# voc_sensor.net
KiCad netlist of a schematic drawn in EAGLE
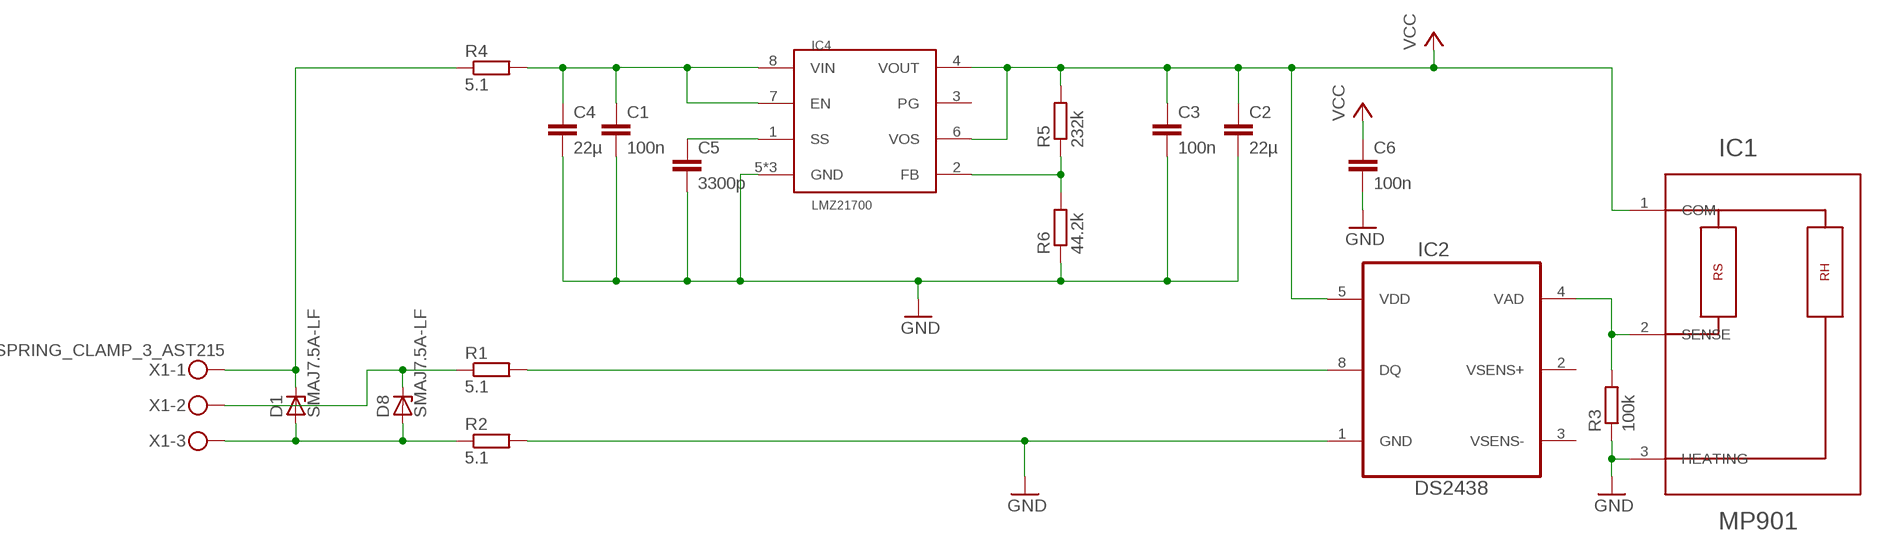
[diagram p0: schematic, sheet 1]

(export (version "E")
  (design (tool "Eeschema 10.0.6"))
  (components
    (comp (ref "C1")
      (value "100n")
      (footprint "eagle-import:C0402")
      (libsource (lib "eagle-import") (part "C-EUC0402"))
    )
    (comp (ref "C2")
      (value "22µ")
      (footprint "eagle-import:C0805K")
      (libsource (lib "eagle-import") (part "C-EUC0805K"))
    )
    (comp (ref "C3")
      (value "100n")
      (footprint "eagle-import:C0402")
      (libsource (lib "eagle-import") (part "C-EUC0402"))
    )
    (comp (ref "C4")
      (value "22µ")
      (footprint "eagle-import:C0805K")
      (libsource (lib "eagle-import") (part "C-EUC0805K"))
    )
    (comp (ref "C5")
      (value "3300p")
      (footprint "eagle-import:C0402")
      (libsource (lib "eagle-import") (part "C-EUC0402"))
    )
    (comp (ref "C6")
      (value "100n")
      (footprint "eagle-import:C0402")
      (libsource (lib "eagle-import") (part "C-EUC0402"))
    )
    (comp (ref "D1")
      (value "SMAJ7.5A-LF")
      (footprint "eagle-import:DO214AC")
      (libsource (lib "eagle-import") (part "ZENER"))
    )
    (comp (ref "D8")
      (value "SMAJ7.5A-LF")
      (footprint "eagle-import:DO214AC")
      (libsource (lib "eagle-import") (part "ZENER"))
    )
    (comp (ref "IC1")
      (value "MP901")
      (footprint "eagle-import:MP901")
      (libsource (lib "eagle-import") (part "MP901"))
    )
    (comp (ref "IC2")
      (value "DS2438")
      (footprint "eagle-import:SO-08")
      (libsource (lib "eagle-import") (part "DS2438"))
    )
    (comp (ref "IC4")
      (value "LMZ21700")
      (footprint "eagle-import:LMZ21700")
      (libsource (lib "eagle-import") (part "LMZ21700"))
    )
    (comp (ref "R1")
      (value "5.1")
      (footprint "eagle-import:R0402")
      (libsource (lib "eagle-import") (part "R-EU_R0402"))
    )
    (comp (ref "R2")
      (value "5.1")
      (footprint "eagle-import:R0402")
      (libsource (lib "eagle-import") (part "R-EU_R0402"))
    )
    (comp (ref "R3")
      (value "100k")
      (footprint "eagle-import:R0402")
      (libsource (lib "eagle-import") (part "R-EU_R0402"))
    )
    (comp (ref "R4")
      (value "5.1")
      (footprint "eagle-import:R0402")
      (libsource (lib "eagle-import") (part "R-EU_R0402"))
    )
    (comp (ref "R5")
      (value "232k")
      (footprint "eagle-import:R0402")
      (libsource (lib "eagle-import") (part "R-EU_R0402"))
    )
    (comp (ref "R6")
      (value "44.2k")
      (footprint "eagle-import:R0402")
      (libsource (lib "eagle-import") (part "R-EU_R0402"))
    )
    (comp (ref "X1")
      (value "SPRING_CLAMP_3_AST215")
      (footprint "eagle-import:AST215_3")
      (libsource (lib "eagle-import") (part "SPRING_CLAMP_3_AST215"))
    )
  )
  (nets
    (net (code "1") (name "GND") (class "Default")
      (node (ref "C1") (pin "2") (pinfunction "2_2") (pintype "passive"))
      (node (ref "C2") (pin "2") (pinfunction "2_2") (pintype "passive"))
      (node (ref "C3") (pin "2") (pinfunction "2_2") (pintype "passive"))
      (node (ref "C4") (pin "2") (pinfunction "2_2") (pintype "passive"))
      (node (ref "C5") (pin "2") (pinfunction "2_2") (pintype "passive"))
      (node (ref "C6") (pin "2") (pinfunction "2_2") (pintype "passive"))
      (node (ref "IC1") (pin "3") (pinfunction "HEATING_3") (pintype "bidirectional"))
      (node (ref "IC2") (pin "1") (pinfunction "GND_1") (pintype "passive"))
      (node (ref "IC4") (pin "5") (pinfunction "GND_5") (pintype "bidirectional"))
      (node (ref "IC4") (pin "TPAD@1") (pinfunction "GND_TPAD@1") (pintype "bidirectional"))
      (node (ref "IC4") (pin "TPAD@2") (pinfunction "GND_TPAD@2") (pintype "bidirectional"))
      (node (ref "R2") (pin "2") (pinfunction "2_2") (pintype "passive"))
      (node (ref "R3") (pin "1") (pinfunction "1_1") (pintype "passive"))
      (node (ref "R6") (pin "1") (pinfunction "1_1") (pintype "passive"))
    )
    (net (code "2") (name "Net-(D1-PadA)") (class "Default")
      (node (ref "D1") (pin "A") (pinfunction "A_A") (pintype "passive"))
      (node (ref "D8") (pin "A") (pinfunction "A_A") (pintype "passive"))
      (node (ref "R2") (pin "1") (pinfunction "1_1") (pintype "passive"))
      (node (ref "X1") (pin "3A") (pinfunction "KL_3A") (pintype "passive"))
      (node (ref "X1") (pin "3B") (pinfunction "KL_3B") (pintype "passive"))
    )
    (net (code "3") (name "Net-(D1-PadC)") (class "Default")
      (node (ref "D1") (pin "C") (pinfunction "C_C") (pintype "passive"))
      (node (ref "R4") (pin "1") (pinfunction "1_1") (pintype "passive"))
      (node (ref "X1") (pin "1A") (pinfunction "KL_1A") (pintype "passive"))
      (node (ref "X1") (pin "1B") (pinfunction "KL_1B") (pintype "passive"))
    )
    (net (code "4") (name "Net-(D8-PadC)") (class "Default")
      (node (ref "D8") (pin "C") (pinfunction "C_C") (pintype "passive"))
      (node (ref "R1") (pin "1") (pinfunction "1_1") (pintype "passive"))
      (node (ref "X1") (pin "2A") (pinfunction "KL_2A") (pintype "passive"))
      (node (ref "X1") (pin "2B") (pinfunction "KL_2B") (pintype "passive"))
    )
    (net (code "5") (name "Net-(IC1-SENSE)") (class "Default")
      (node (ref "IC1") (pin "2") (pinfunction "SENSE_2") (pintype "bidirectional"))
      (node (ref "IC2") (pin "4") (pinfunction "VAD_4") (pintype "input"))
      (node (ref "R3") (pin "2") (pinfunction "2_2") (pintype "passive"))
    )
    (net (code "6") (name "Net-(IC2-DQ)") (class "Default")
      (node (ref "IC2") (pin "8") (pinfunction "DQ_8") (pintype "bidirectional"))
      (node (ref "R1") (pin "2") (pinfunction "2_2") (pintype "passive"))
    )
    (net (code "7") (name "Net-(IC4-EN)") (class "Default")
      (node (ref "C1") (pin "1") (pinfunction "1_1") (pintype "passive"))
      (node (ref "C4") (pin "1") (pinfunction "1_1") (pintype "passive"))
      (node (ref "IC4") (pin "7") (pinfunction "EN_7") (pintype "bidirectional"))
      (node (ref "IC4") (pin "8") (pinfunction "VIN_8") (pintype "bidirectional"))
      (node (ref "R4") (pin "2") (pinfunction "2_2") (pintype "passive"))
    )
    (net (code "8") (name "Net-(IC4-FB)") (class "Default")
      (node (ref "IC4") (pin "2") (pinfunction "FB_2") (pintype "bidirectional"))
      (node (ref "R5") (pin "1") (pinfunction "1_1") (pintype "passive"))
      (node (ref "R6") (pin "2") (pinfunction "2_2") (pintype "passive"))
    )
    (net (code "9") (name "Net-(IC4-SS)") (class "Default")
      (node (ref "C5") (pin "1") (pinfunction "1_1") (pintype "passive"))
      (node (ref "IC4") (pin "1") (pinfunction "SS_1") (pintype "bidirectional"))
    )
    (net (code "10") (name "VCC") (class "Default")
      (node (ref "C2") (pin "1") (pinfunction "1_1") (pintype "passive"))
      (node (ref "C3") (pin "1") (pinfunction "1_1") (pintype "passive"))
      (node (ref "C6") (pin "1") (pinfunction "1_1") (pintype "passive"))
      (node (ref "IC1") (pin "1") (pinfunction "COM_1") (pintype "bidirectional"))
      (node (ref "IC2") (pin "5") (pinfunction "VDD_5") (pintype "power_in"))
      (node (ref "IC4") (pin "4") (pinfunction "VOUT_4") (pintype "bidirectional"))
      (node (ref "IC4") (pin "6") (pinfunction "VOS_6") (pintype "bidirectional"))
      (node (ref "R5") (pin "2") (pinfunction "2_2") (pintype "passive"))
    )
    (net (code "11") (name "unconnected-(IC2-VSENS+-Pad2)") (class "Default")
      (node (ref "IC2") (pin "2") (pinfunction "VSENS+_2") (pintype "input"))
    )
    (net (code "12") (name "unconnected-(IC2-VSENS--Pad3)") (class "Default")
      (node (ref "IC2") (pin "3") (pinfunction "VSENS-_3") (pintype "input"))
    )
    (net (code "13") (name "unconnected-(IC4-PG-Pad3)") (class "Default")
      (node (ref "IC4") (pin "3") (pinfunction "PG_3") (pintype "bidirectional"))
    )
  )
)
